# ADXL377_Breakout.net
KiCad netlist of a schematic drawn in EAGLE
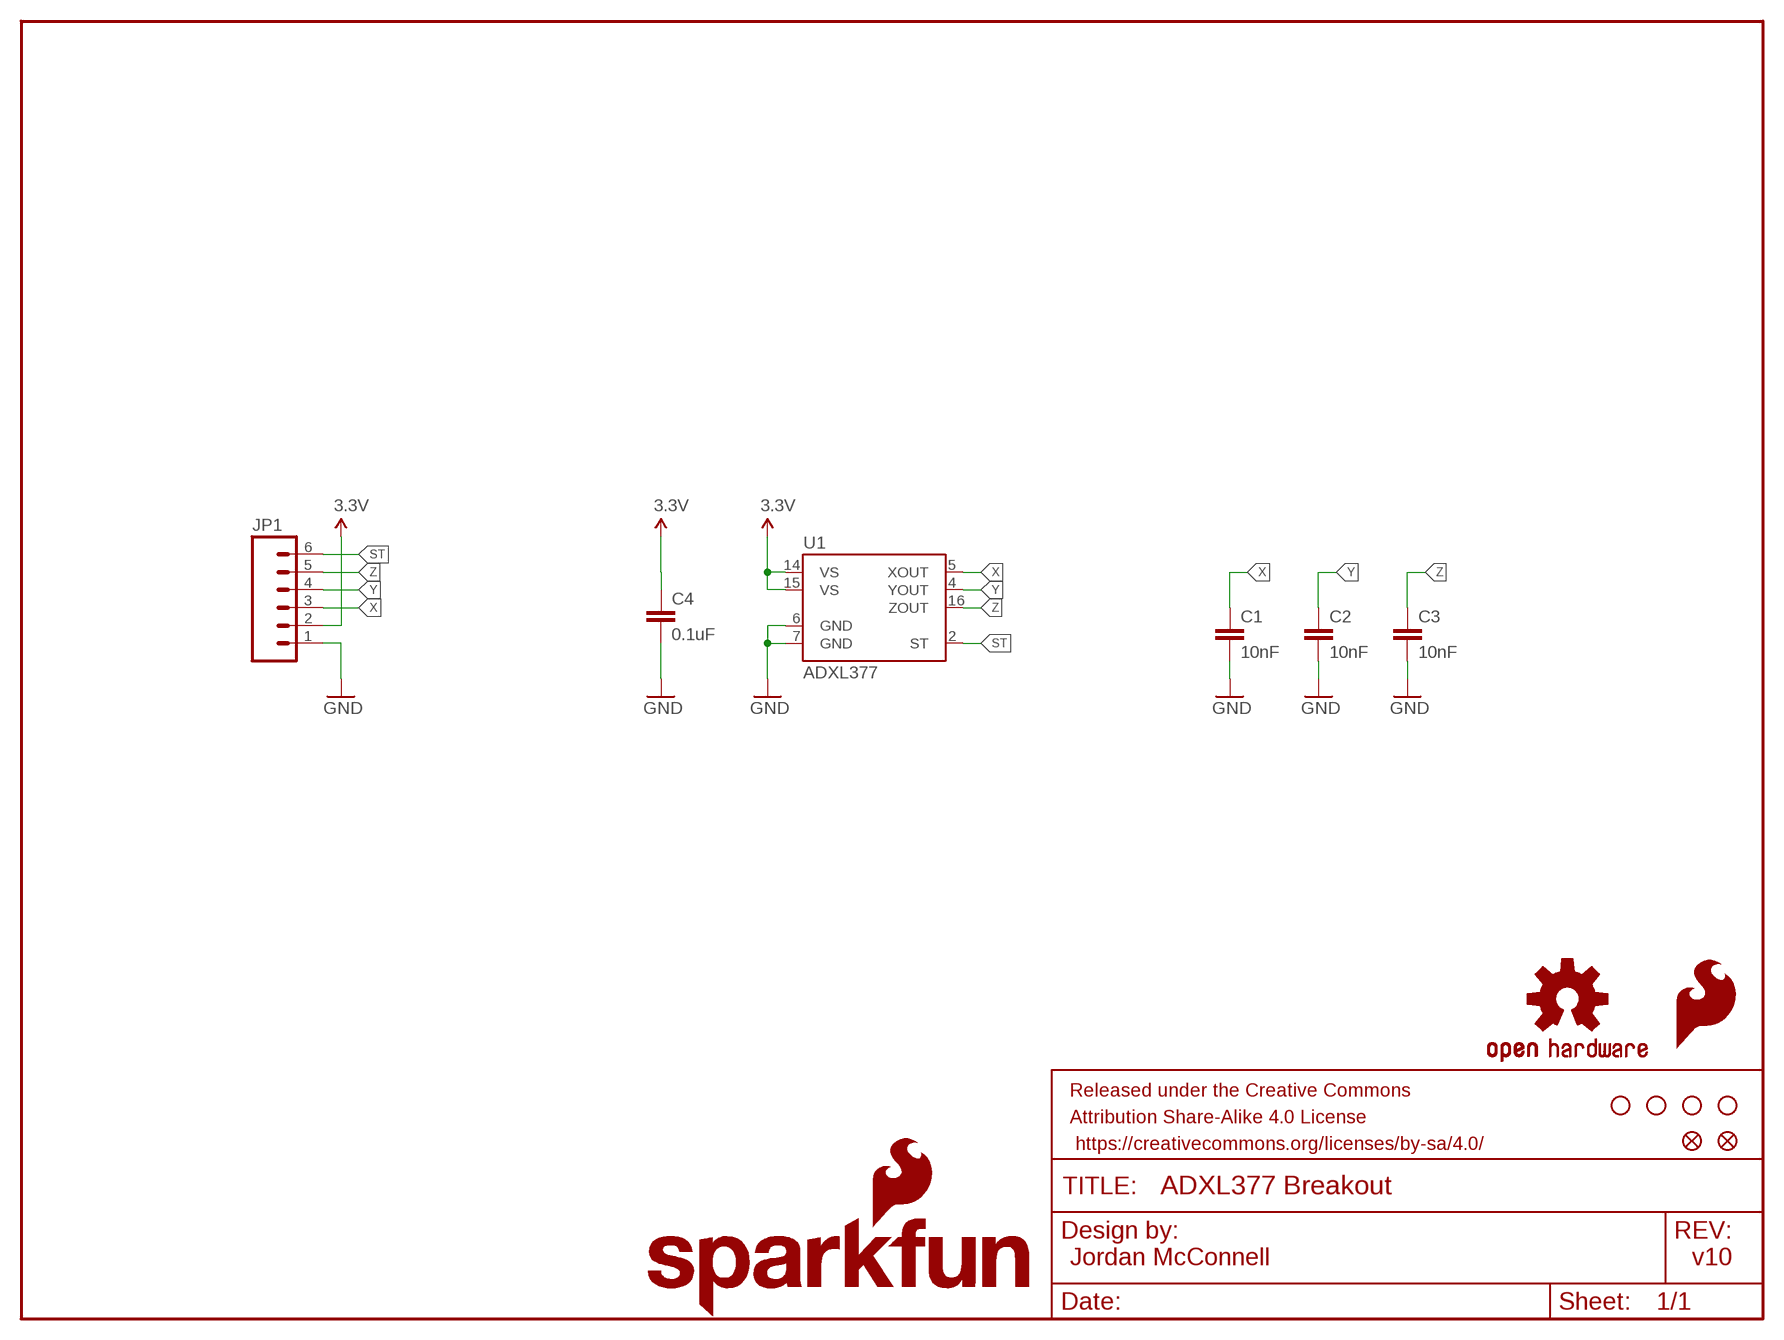
[diagram p0: schematic, sheet 1]

(export (version "E")
  (design (tool "Eeschema 10.0.6"))
  (components
    (comp (ref "C1")
      (value "10nF")
      (footprint "eagle-import:0603-CAP")
      (libsource (lib "eagle-import") (part "10NF/10000PF-50V-10%(0603)"))
    )
    (comp (ref "C2")
      (value "10nF")
      (footprint "eagle-import:0603-CAP")
      (libsource (lib "eagle-import") (part "10NF/10000PF-50V-10%(0603)"))
    )
    (comp (ref "C3")
      (value "10nF")
      (footprint "eagle-import:0603-CAP")
      (libsource (lib "eagle-import") (part "10NF/10000PF-50V-10%(0603)"))
    )
    (comp (ref "C4")
      (value "0.1uF")
      (footprint "eagle-import:0603-CAP")
      (libsource (lib "eagle-import") (part "0.1UF-25V(+80/-20%)(0603)"))
    )
    (comp (ref "FID1")
      (value "FIDUCIAL1X2")
      (footprint "eagle-import:FIDUCIAL-1X2")
      (libsource (lib "eagle-import") (part "FIDUCIAL1X2"))
    )
    (comp (ref "FID2")
      (value "FIDUCIAL1X2")
      (footprint "eagle-import:FIDUCIAL-1X2")
      (libsource (lib "eagle-import") (part "FIDUCIAL1X2"))
    )
    (comp (ref "FRAME1")
      (value "FRAME-LETTER")
      (footprint "eagle-import:CREATIVE_COMMONS")
      (libsource (lib "eagle-import") (part "FRAME-LETTER"))
    )
    (comp (ref "JP1")
      (value "M06SIP")
      (footprint "eagle-import:1X06")
      (libsource (lib "eagle-import") (part "M06SIP"))
    )
    (comp (ref "LOGO1")
      (value "SFE_LOGO_FLAME.1_INCH")
      (footprint "eagle-import:SFE_LOGO_FLAME_.1")
      (libsource (lib "eagle-import") (part "SFE_LOGO_FLAME.1_INCH"))
    )
    (comp (ref "LOGO2")
      (value "OSHW-LOGOS")
      (footprint "eagle-import:OSHW-LOGO-S")
      (libsource (lib "eagle-import") (part "OSHW-LOGOS"))
    )
    (comp (ref "LOGO5")
      (value "SFE_LOGO_NAME_FLAME.1_INCH")
      (footprint "eagle-import:SFE_LOGO_NAME_FLAME_.1")
      (libsource (lib "eagle-import") (part "SFE_LOGO_NAME_FLAME.1_INCH"))
    )
    (comp (ref "STANDOFF1")
      (value "STAND-OFF")
      (footprint "eagle-import:STAND-OFF")
      (libsource (lib "eagle-import") (part "STAND-OFF"))
    )
    (comp (ref "STANDOFF2")
      (value "STAND-OFF")
      (footprint "eagle-import:STAND-OFF")
      (libsource (lib "eagle-import") (part "STAND-OFF"))
    )
    (comp (ref "STANDOFF3")
      (value "STAND-OFF")
      (footprint "eagle-import:STAND-OFF")
      (libsource (lib "eagle-import") (part "STAND-OFF"))
    )
    (comp (ref "STANDOFF4")
      (value "STAND-OFF")
      (footprint "eagle-import:STAND-OFF")
      (libsource (lib "eagle-import") (part "STAND-OFF"))
    )
    (comp (ref "U1")
      (value "ADXL377")
      (footprint "eagle-import:LFCSP_LQ-16")
      (libsource (lib "eagle-import") (part "ADXL377"))
    )
  )
  (nets
    (net (code "1") (name "3.3V") (class "Default")
      (node (ref "C4") (pin "1") (pinfunction "1_1") (pintype "passive"))
      (node (ref "JP1") (pin "2") (pinfunction "2_2") (pintype "passive"))
      (node (ref "U1") (pin "14") (pinfunction "VS_14") (pintype "bidirectional"))
      (node (ref "U1") (pin "15") (pinfunction "VS_15") (pintype "bidirectional"))
    )
    (net (code "2") (name "GND") (class "Default")
      (node (ref "C1") (pin "2") (pinfunction "2_2") (pintype "passive"))
      (node (ref "C2") (pin "2") (pinfunction "2_2") (pintype "passive"))
      (node (ref "C3") (pin "2") (pinfunction "2_2") (pintype "passive"))
      (node (ref "C4") (pin "2") (pinfunction "2_2") (pintype "passive"))
      (node (ref "JP1") (pin "1") (pinfunction "1_1") (pintype "passive"))
      (node (ref "U1") (pin "6") (pinfunction "GND_6") (pintype "bidirectional"))
      (node (ref "U1") (pin "7") (pinfunction "GND_7") (pintype "bidirectional"))
    )
    (net (code "3") (name "ST") (class "Default")
      (node (ref "JP1") (pin "6") (pinfunction "6_6") (pintype "passive"))
      (node (ref "U1") (pin "2") (pinfunction "ST_2") (pintype "bidirectional"))
    )
    (net (code "4") (name "X") (class "Default")
      (node (ref "C1") (pin "1") (pinfunction "1_1") (pintype "passive"))
      (node (ref "JP1") (pin "3") (pinfunction "3_3") (pintype "passive"))
      (node (ref "U1") (pin "5") (pinfunction "XOUT_5") (pintype "bidirectional"))
    )
    (net (code "5") (name "Y") (class "Default")
      (node (ref "C2") (pin "1") (pinfunction "1_1") (pintype "passive"))
      (node (ref "JP1") (pin "4") (pinfunction "4_4") (pintype "passive"))
      (node (ref "U1") (pin "4") (pinfunction "YOUT_4") (pintype "bidirectional"))
    )
    (net (code "6") (name "Z") (class "Default")
      (node (ref "C3") (pin "1") (pinfunction "1_1") (pintype "passive"))
      (node (ref "JP1") (pin "5") (pinfunction "5_5") (pintype "passive"))
      (node (ref "U1") (pin "16") (pinfunction "ZOUT_16") (pintype "bidirectional"))
    )
  )
)
